# weather-sensor.net
KiCad netlist of a schematic drawn in EAGLE
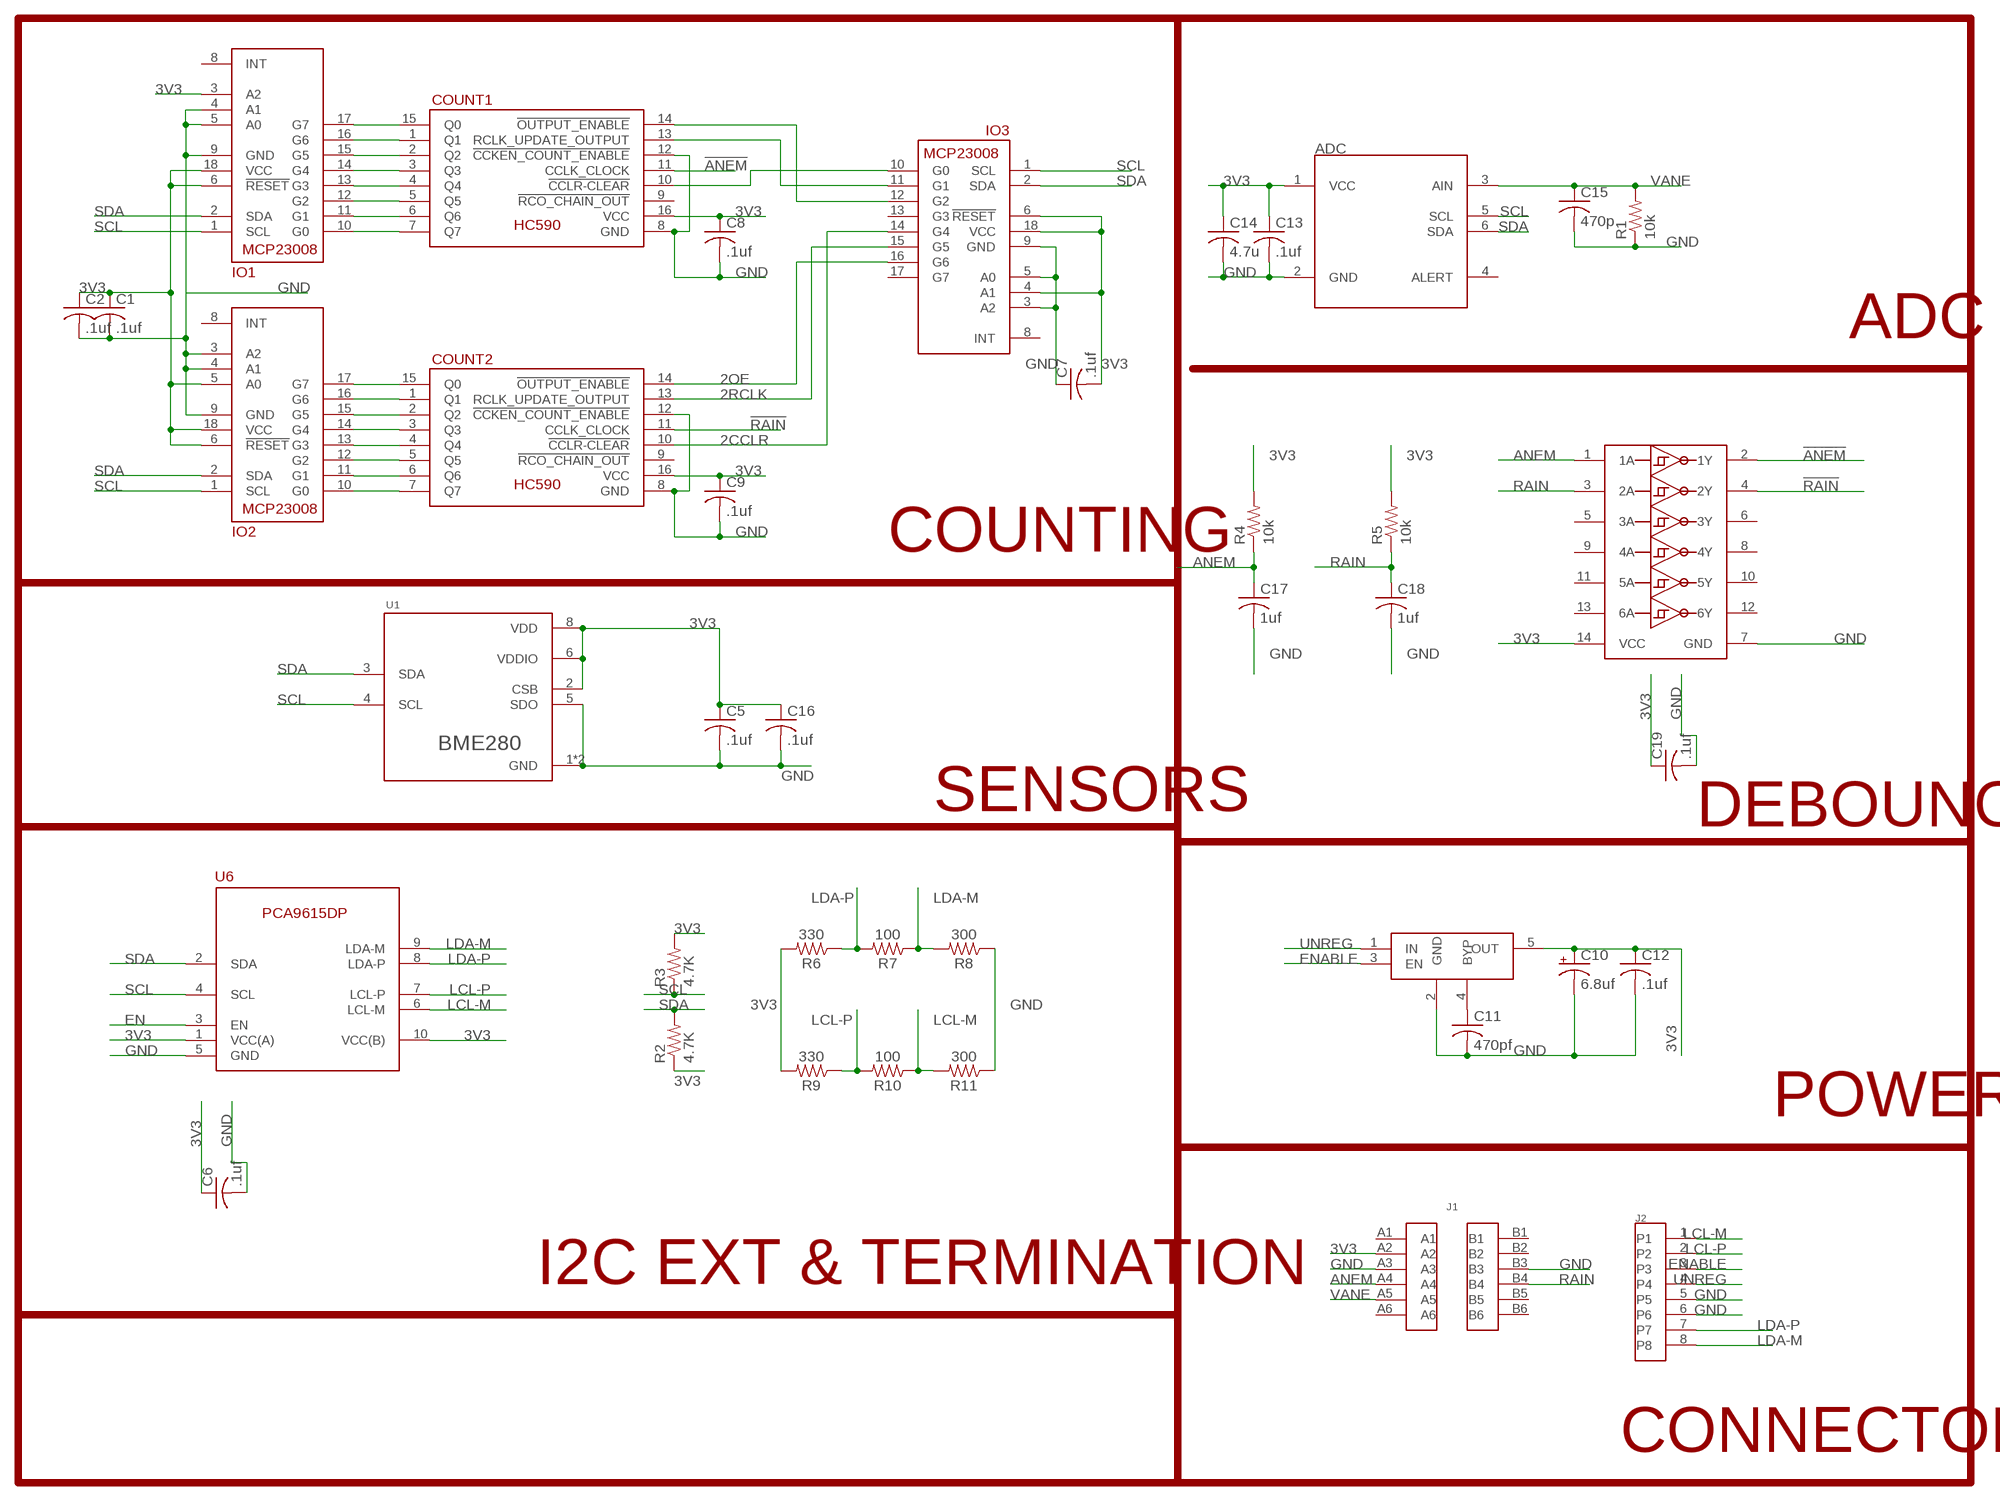
[diagram p0: schematic, sheet 1]

(export (version "E")
  (design (tool "Eeschema 10.0.6"))
  (components
    (comp (ref "ADC")
      (value "ADC081C021SOT-DDC")
      (footprint "eagle-import:SOP95P280X110-6")
      (libsource (lib "eagle-import") (part "ADC081C021SOT-DDC"))
    )
    (comp (ref "C1")
      (value ".1uf")
      (footprint "eagle-import:C0603K")
      (libsource (lib "eagle-import") (part "C-USC0603K"))
    )
    (comp (ref "C2")
      (value ".1uf")
      (footprint "eagle-import:C0603K")
      (libsource (lib "eagle-import") (part "C-USC0603K"))
    )
    (comp (ref "C5")
      (value ".1uf")
      (footprint "eagle-import:C0603K")
      (libsource (lib "eagle-import") (part "C-USC0603K"))
    )
    (comp (ref "C6")
      (value ".1uf")
      (footprint "eagle-import:C0603K")
      (libsource (lib "eagle-import") (part "C-USC0603K"))
    )
    (comp (ref "C7")
      (value ".1uf")
      (footprint "eagle-import:C0603K")
      (libsource (lib "eagle-import") (part "C-USC0603K"))
    )
    (comp (ref "C8")
      (value ".1uf")
      (footprint "eagle-import:C0603K")
      (libsource (lib "eagle-import") (part "C-USC0603K"))
    )
    (comp (ref "C9")
      (value ".1uf")
      (footprint "eagle-import:C0603K")
      (libsource (lib "eagle-import") (part "C-USC0603K"))
    )
    (comp (ref "C10")
      (value "6.8uf")
      (footprint "eagle-import:A_3216-18R")
      (libsource (lib "eagle-import") (part "CPOL-USA/3216-18R"))
    )
    (comp (ref "C11")
      (value "470pf")
      (footprint "eagle-import:C0603K")
      (libsource (lib "eagle-import") (part "C-USC0603K"))
    )
    (comp (ref "C12")
      (value ".1uf")
      (footprint "eagle-import:C0603K")
      (libsource (lib "eagle-import") (part "C-USC0603K"))
    )
    (comp (ref "C13")
      (value ".1uf")
      (footprint "eagle-import:C0603K")
      (libsource (lib "eagle-import") (part "C-USC0603K"))
    )
    (comp (ref "C14")
      (value "4.7u")
      (footprint "eagle-import:C0603K")
      (libsource (lib "eagle-import") (part "C-USC0603K"))
    )
    (comp (ref "C15")
      (value "470p")
      (footprint "eagle-import:C0603K")
      (libsource (lib "eagle-import") (part "C-USC0603K"))
    )
    (comp (ref "C16")
      (value ".1uf")
      (footprint "eagle-import:C0603K")
      (libsource (lib "eagle-import") (part "C-USC0603K"))
    )
    (comp (ref "C17")
      (value "1uf")
      (footprint "eagle-import:C0603K")
      (libsource (lib "eagle-import") (part "C-USC0603K"))
    )
    (comp (ref "C18")
      (value "1uf")
      (footprint "eagle-import:C0603K")
      (libsource (lib "eagle-import") (part "C-USC0603K"))
    )
    (comp (ref "C19")
      (value ".1uf")
      (footprint "eagle-import:C0603K")
      (libsource (lib "eagle-import") (part "C-USC0603K"))
    )
    (comp (ref "COUNT1")
      (value "74HC590")
      (footprint "eagle-import:SOIC127P1050X265-16")
      (libsource (lib "eagle-import") (part "74HC590"))
    )
    (comp (ref "COUNT2")
      (value "74HC590")
      (footprint "eagle-import:SOIC127P1050X265-16")
      (libsource (lib "eagle-import") (part "74HC590"))
    )
    (comp (ref "INVERTER")
      (value "74HC14")
      (footprint "eagle-import:SOIC127P780X200-14")
      (libsource (lib "eagle-import") (part "74HC14"))
    )
    (comp (ref "IO1")
      (value "MCP23008")
      (footprint "eagle-import:SOIC18-W")
      (libsource (lib "eagle-import") (part "MCP23008"))
    )
    (comp (ref "IO2")
      (value "MCP23008")
      (footprint "eagle-import:SOIC18-W")
      (libsource (lib "eagle-import") (part "MCP23008"))
    )
    (comp (ref "IO3")
      (value "MCP23008")
      (footprint "eagle-import:SOIC18-W")
      (libsource (lib "eagle-import") (part "MCP23008"))
    )
    (comp (ref "J1")
      (value "43841-0005")
      (footprint "eagle-import:43841-0005")
      (libsource (lib "eagle-import") (part "43841-0005"))
    )
    (comp (ref "J2")
      (value "95501-6889")
      (footprint "eagle-import:95501-6889")
      (libsource (lib "eagle-import") (part "95501-6889"))
    )
    (comp (ref "R1")
      (value "10k")
      (footprint "eagle-import:R0603")
      (libsource (lib "eagle-import") (part "R-US_R0603"))
    )
    (comp (ref "R2")
      (value "4.7K")
      (footprint "eagle-import:R0603")
      (libsource (lib "eagle-import") (part "R-US_R0603"))
    )
    (comp (ref "R3")
      (value "4.7K")
      (footprint "eagle-import:R0603")
      (libsource (lib "eagle-import") (part "R-US_R0603"))
    )
    (comp (ref "R4")
      (value "10k")
      (footprint "eagle-import:R0603")
      (libsource (lib "eagle-import") (part "R-US_R0603"))
    )
    (comp (ref "R5")
      (value "10k")
      (footprint "eagle-import:R0603")
      (libsource (lib "eagle-import") (part "R-US_R0603"))
    )
    (comp (ref "R6")
      (value "330")
      (footprint "eagle-import:0603")
      (libsource (lib "eagle-import") (part "100KOHM-0603-1/10W-1%"))
    )
    (comp (ref "R7")
      (value "100")
      (footprint "eagle-import:0603")
      (libsource (lib "eagle-import") (part "100KOHM-0603-1/10W-1%"))
    )
    (comp (ref "R8")
      (value "300")
      (footprint "eagle-import:0603")
      (libsource (lib "eagle-import") (part "100KOHM-0603-1/10W-1%"))
    )
    (comp (ref "R9")
      (value "330")
      (footprint "eagle-import:0603")
      (libsource (lib "eagle-import") (part "100KOHM-0603-1/10W-1%"))
    )
    (comp (ref "R10")
      (value "100")
      (footprint "eagle-import:0603")
      (libsource (lib "eagle-import") (part "100KOHM-0603-1/10W-1%"))
    )
    (comp (ref "R11")
      (value "300")
      (footprint "eagle-import:0603")
      (libsource (lib "eagle-import") (part "100KOHM-0603-1/10W-1%"))
    )
    (comp (ref "U1")
      (value "BME280")
      (footprint "eagle-import:BM280")
      (libsource (lib "eagle-import") (part "BME280"))
    )
    (comp (ref "U5")
      (value "MIC5219-3.3YM5-TR")
      (footprint "eagle-import:SOT95P280X145-5")
      (libsource (lib "eagle-import") (part "MIC5219-3.3YM5-TR"))
    )
    (comp (ref "U6")
      (value "PCA9615")
      (footprint "eagle-import:SOP50P490X110-10")
      (libsource (lib "eagle-import") (part "PCA9615"))
    )
  )
  (nets
    (net (code "1") (name "/2CCLR") (class "Default")
      (node (ref "COUNT2") (pin "10") (pinfunction "~{CCLR-CLEAR}_10") (pintype "bidirectional"))
      (node (ref "IO3") (pin "14") (pinfunction "G4_14") (pintype "bidirectional"))
    )
    (net (code "2") (name "/2OE") (class "Default")
      (node (ref "COUNT2") (pin "14") (pinfunction "~{OUTPUT_ENABLE}_14") (pintype "bidirectional"))
      (node (ref "IO3") (pin "16") (pinfunction "G6_16") (pintype "bidirectional"))
    )
    (net (code "3") (name "/2RCLK") (class "Default")
      (node (ref "COUNT2") (pin "13") (pinfunction "RCLK_UPDATE_OUTPUT_13") (pintype "bidirectional"))
      (node (ref "IO3") (pin "15") (pinfunction "G5_15") (pintype "bidirectional"))
    )
    (net (code "4") (name "/3V3") (class "Default")
      (node (ref "ADC") (pin "1") (pinfunction "VCC_1") (pintype "bidirectional"))
      (node (ref "C1") (pin "1") (pinfunction "1_1") (pintype "passive"))
      (node (ref "C10") (pin "+") (pinfunction "+_+") (pintype "passive"))
      (node (ref "C12") (pin "1") (pinfunction "1_1") (pintype "passive"))
      (node (ref "C13") (pin "1") (pinfunction "1_1") (pintype "passive"))
      (node (ref "C14") (pin "1") (pinfunction "1_1") (pintype "passive"))
      (node (ref "C16") (pin "1") (pinfunction "1_1") (pintype "passive"))
      (node (ref "C19") (pin "1") (pinfunction "1_1") (pintype "passive"))
      (node (ref "C2") (pin "1") (pinfunction "1_1") (pintype "passive"))
      (node (ref "C5") (pin "1") (pinfunction "1_1") (pintype "passive"))
      (node (ref "C6") (pin "1") (pinfunction "1_1") (pintype "passive"))
      (node (ref "C7") (pin "2") (pinfunction "2_2") (pintype "passive"))
      (node (ref "C8") (pin "1") (pinfunction "1_1") (pintype "passive"))
      (node (ref "C9") (pin "1") (pinfunction "1_1") (pintype "passive"))
      (node (ref "COUNT1") (pin "16") (pinfunction "VCC_16") (pintype "bidirectional"))
      (node (ref "COUNT2") (pin "16") (pinfunction "VCC_16") (pintype "bidirectional"))
      (node (ref "INVERTER") (pin "14") (pinfunction "VCC_14") (pintype "bidirectional"))
      (node (ref "IO1") (pin "18") (pinfunction "VCC_18") (pintype "bidirectional"))
      (node (ref "IO1") (pin "3") (pinfunction "A2_3") (pintype "bidirectional"))
      (node (ref "IO1") (pin "6") (pinfunction "~{RESET}_6") (pintype "bidirectional"))
      (node (ref "IO2") (pin "18") (pinfunction "VCC_18") (pintype "bidirectional"))
      (node (ref "IO2") (pin "5") (pinfunction "A0_5") (pintype "bidirectional"))
      (node (ref "IO2") (pin "6") (pinfunction "~{RESET}_6") (pintype "bidirectional"))
      (node (ref "IO3") (pin "18") (pinfunction "VCC_18") (pintype "bidirectional"))
      (node (ref "IO3") (pin "4") (pinfunction "A1_4") (pintype "bidirectional"))
      (node (ref "IO3") (pin "6") (pinfunction "~{RESET}_6") (pintype "bidirectional"))
      (node (ref "J1") (pin "A2") (pinfunction "A2_A2") (pintype "bidirectional"))
      (node (ref "R2") (pin "1") (pinfunction "1_1") (pintype "passive"))
      (node (ref "R3") (pin "2") (pinfunction "2_2") (pintype "passive"))
      (node (ref "R4") (pin "2") (pinfunction "2_2") (pintype "passive"))
      (node (ref "R5") (pin "2") (pinfunction "2_2") (pintype "passive"))
      (node (ref "R6") (pin "2") (pinfunction "2_2") (pintype "passive"))
      (node (ref "R9") (pin "2") (pinfunction "2_2") (pintype "passive"))
      (node (ref "U1") (pin "2") (pinfunction "CSB_2") (pintype "bidirectional"))
      (node (ref "U1") (pin "6") (pinfunction "VDDIO_6") (pintype "bidirectional"))
      (node (ref "U1") (pin "8") (pinfunction "VDD_8") (pintype "bidirectional"))
      (node (ref "U5") (pin "5") (pinfunction "OUT_5") (pintype "bidirectional"))
      (node (ref "U6") (pin "1") (pinfunction "VCC(A)_1") (pintype "bidirectional"))
      (node (ref "U6") (pin "10") (pinfunction "VCC(B)_10") (pintype "bidirectional"))
    )
    (net (code "5") (name "/ANEM") (class "Default")
      (node (ref "C17") (pin "1") (pinfunction "1_1") (pintype "passive"))
      (node (ref "INVERTER") (pin "1") (pinfunction "1A_1") (pintype "bidirectional"))
      (node (ref "J1") (pin "A4") (pinfunction "A4_A4") (pintype "bidirectional"))
      (node (ref "R4") (pin "1") (pinfunction "1_1") (pintype "passive"))
    )
    (net (code "6") (name "/EN") (class "Default")
      (node (ref "U6") (pin "3") (pinfunction "EN_3") (pintype "bidirectional"))
    )
    (net (code "7") (name "/ENABLE") (class "Default")
      (node (ref "J2") (pin "3") (pinfunction "P3_3") (pintype "bidirectional"))
      (node (ref "U5") (pin "3") (pinfunction "EN_3") (pintype "bidirectional"))
    )
    (net (code "8") (name "/GND") (class "Default")
      (node (ref "ADC") (pin "2") (pinfunction "GND_2") (pintype "bidirectional"))
      (node (ref "C1") (pin "2") (pinfunction "2_2") (pintype "passive"))
      (node (ref "C10") (pin "-") (pinfunction "-_-") (pintype "passive"))
      (node (ref "C11") (pin "2") (pinfunction "2_2") (pintype "passive"))
      (node (ref "C12") (pin "2") (pinfunction "2_2") (pintype "passive"))
      (node (ref "C13") (pin "2") (pinfunction "2_2") (pintype "passive"))
      (node (ref "C14") (pin "2") (pinfunction "2_2") (pintype "passive"))
      (node (ref "C15") (pin "2") (pinfunction "2_2") (pintype "passive"))
      (node (ref "C16") (pin "2") (pinfunction "2_2") (pintype "passive"))
      (node (ref "C17") (pin "2") (pinfunction "2_2") (pintype "passive"))
      (node (ref "C18") (pin "2") (pinfunction "2_2") (pintype "passive"))
      (node (ref "C19") (pin "2") (pinfunction "2_2") (pintype "passive"))
      (node (ref "C2") (pin "2") (pinfunction "2_2") (pintype "passive"))
      (node (ref "C5") (pin "2") (pinfunction "2_2") (pintype "passive"))
      (node (ref "C6") (pin "2") (pinfunction "2_2") (pintype "passive"))
      (node (ref "C7") (pin "1") (pinfunction "1_1") (pintype "passive"))
      (node (ref "C8") (pin "2") (pinfunction "2_2") (pintype "passive"))
      (node (ref "C9") (pin "2") (pinfunction "2_2") (pintype "passive"))
      (node (ref "COUNT1") (pin "12") (pinfunction "~{CCKEN_COUNT_ENABLE}_12") (pintype "bidirectional"))
      (node (ref "COUNT1") (pin "8") (pinfunction "GND_8") (pintype "bidirectional"))
      (node (ref "COUNT2") (pin "12") (pinfunction "~{CCKEN_COUNT_ENABLE}_12") (pintype "bidirectional"))
      (node (ref "COUNT2") (pin "8") (pinfunction "GND_8") (pintype "bidirectional"))
      (node (ref "INVERTER") (pin "7") (pinfunction "GND_7") (pintype "bidirectional"))
      (node (ref "IO1") (pin "4") (pinfunction "A1_4") (pintype "bidirectional"))
      (node (ref "IO1") (pin "5") (pinfunction "A0_5") (pintype "bidirectional"))
      (node (ref "IO1") (pin "9") (pinfunction "GND_9") (pintype "bidirectional"))
      (node (ref "IO2") (pin "3") (pinfunction "A2_3") (pintype "bidirectional"))
      (node (ref "IO2") (pin "4") (pinfunction "A1_4") (pintype "bidirectional"))
      (node (ref "IO2") (pin "9") (pinfunction "GND_9") (pintype "bidirectional"))
      (node (ref "IO3") (pin "3") (pinfunction "A2_3") (pintype "bidirectional"))
      (node (ref "IO3") (pin "5") (pinfunction "A0_5") (pintype "bidirectional"))
      (node (ref "IO3") (pin "9") (pinfunction "GND_9") (pintype "bidirectional"))
      (node (ref "J1") (pin "A3") (pinfunction "A3_A3") (pintype "bidirectional"))
      (node (ref "J1") (pin "B3") (pinfunction "B3_B3") (pintype "bidirectional"))
      (node (ref "J2") (pin "5") (pinfunction "P5_5") (pintype "bidirectional"))
      (node (ref "J2") (pin "6") (pinfunction "P6_6") (pintype "bidirectional"))
      (node (ref "R1") (pin "1") (pinfunction "1_1") (pintype "passive"))
      (node (ref "R11") (pin "1") (pinfunction "1_1") (pintype "passive"))
      (node (ref "R8") (pin "1") (pinfunction "1_1") (pintype "passive"))
      (node (ref "U1") (pin "1") (pinfunction "GND_1") (pintype "bidirectional"))
      (node (ref "U1") (pin "5") (pinfunction "SDO_5") (pintype "bidirectional"))
      (node (ref "U1") (pin "7") (pinfunction "GND_7") (pintype "bidirectional"))
      (node (ref "U5") (pin "2") (pinfunction "GND_2") (pintype "bidirectional"))
      (node (ref "U6") (pin "5") (pinfunction "GND_5") (pintype "bidirectional"))
    )
    (net (code "9") (name "/LCL-M") (class "Default")
      (node (ref "J2") (pin "1") (pinfunction "P1_1") (pintype "bidirectional"))
      (node (ref "R10") (pin "1") (pinfunction "1_1") (pintype "passive"))
      (node (ref "R11") (pin "2") (pinfunction "2_2") (pintype "passive"))
      (node (ref "U6") (pin "6") (pinfunction "LCL-M_6") (pintype "bidirectional"))
    )
    (net (code "10") (name "/LCL-P") (class "Default")
      (node (ref "J2") (pin "2") (pinfunction "P2_2") (pintype "bidirectional"))
      (node (ref "R10") (pin "2") (pinfunction "2_2") (pintype "passive"))
      (node (ref "R9") (pin "1") (pinfunction "1_1") (pintype "passive"))
      (node (ref "U6") (pin "7") (pinfunction "LCL-P_7") (pintype "bidirectional"))
    )
    (net (code "11") (name "/LDA-M") (class "Default")
      (node (ref "J2") (pin "8") (pinfunction "P8_8") (pintype "bidirectional"))
      (node (ref "R7") (pin "1") (pinfunction "1_1") (pintype "passive"))
      (node (ref "R8") (pin "2") (pinfunction "2_2") (pintype "passive"))
      (node (ref "U6") (pin "9") (pinfunction "LDA-M_9") (pintype "bidirectional"))
    )
    (net (code "12") (name "/LDA-P") (class "Default")
      (node (ref "J2") (pin "7") (pinfunction "P7_7") (pintype "bidirectional"))
      (node (ref "R6") (pin "1") (pinfunction "1_1") (pintype "passive"))
      (node (ref "R7") (pin "2") (pinfunction "2_2") (pintype "passive"))
      (node (ref "U6") (pin "8") (pinfunction "LDA-P_8") (pintype "bidirectional"))
    )
    (net (code "13") (name "/RAIN") (class "Default")
      (node (ref "C18") (pin "1") (pinfunction "1_1") (pintype "passive"))
      (node (ref "INVERTER") (pin "3") (pinfunction "2A_3") (pintype "bidirectional"))
      (node (ref "J1") (pin "B4") (pinfunction "B4_B4") (pintype "bidirectional"))
      (node (ref "R5") (pin "1") (pinfunction "1_1") (pintype "passive"))
    )
    (net (code "14") (name "/SCL") (class "Default")
      (node (ref "ADC") (pin "5") (pinfunction "SCL_5") (pintype "bidirectional"))
      (node (ref "IO1") (pin "1") (pinfunction "SCL_1") (pintype "bidirectional"))
      (node (ref "IO2") (pin "1") (pinfunction "SCL_1") (pintype "bidirectional"))
      (node (ref "IO3") (pin "1") (pinfunction "SCL_1") (pintype "bidirectional"))
      (node (ref "R3") (pin "1") (pinfunction "1_1") (pintype "passive"))
      (node (ref "U1") (pin "4") (pinfunction "SCL_4") (pintype "bidirectional"))
      (node (ref "U6") (pin "4") (pinfunction "SCL_4") (pintype "bidirectional"))
    )
    (net (code "15") (name "/SDA") (class "Default")
      (node (ref "ADC") (pin "6") (pinfunction "SDA_6") (pintype "bidirectional"))
      (node (ref "IO1") (pin "2") (pinfunction "SDA_2") (pintype "bidirectional"))
      (node (ref "IO2") (pin "2") (pinfunction "SDA_2") (pintype "bidirectional"))
      (node (ref "IO3") (pin "2") (pinfunction "SDA_2") (pintype "bidirectional"))
      (node (ref "R2") (pin "2") (pinfunction "2_2") (pintype "passive"))
      (node (ref "U1") (pin "3") (pinfunction "SDA_3") (pintype "bidirectional"))
      (node (ref "U6") (pin "2") (pinfunction "SDA_2") (pintype "bidirectional"))
    )
    (net (code "16") (name "/UNREG") (class "Default")
      (node (ref "J2") (pin "4") (pinfunction "P4_4") (pintype "bidirectional"))
      (node (ref "U5") (pin "1") (pinfunction "IN_1") (pintype "bidirectional"))
    )
    (net (code "17") (name "/VANE") (class "Default")
      (node (ref "ADC") (pin "3") (pinfunction "AIN_3") (pintype "bidirectional"))
      (node (ref "C15") (pin "1") (pinfunction "1_1") (pintype "passive"))
      (node (ref "J1") (pin "A5") (pinfunction "A5_A5") (pintype "bidirectional"))
      (node (ref "R1") (pin "2") (pinfunction "2_2") (pintype "passive"))
    )
    (net (code "18") (name "/~{ANEM}") (class "Default")
      (node (ref "COUNT1") (pin "11") (pinfunction "CCLK_CLOCK_11") (pintype "bidirectional"))
      (node (ref "INVERTER") (pin "2") (pinfunction "1Y_2") (pintype "bidirectional"))
    )
    (net (code "19") (name "/~{RAIN}") (class "Default")
      (node (ref "COUNT2") (pin "11") (pinfunction "CCLK_CLOCK_11") (pintype "bidirectional"))
      (node (ref "INVERTER") (pin "4") (pinfunction "2Y_4") (pintype "bidirectional"))
    )
    (net (code "20") (name "Net-(COUNT1-Q0)") (class "Default")
      (node (ref "COUNT1") (pin "15") (pinfunction "Q0_15") (pintype "bidirectional"))
      (node (ref "IO1") (pin "17") (pinfunction "G7_17") (pintype "bidirectional"))
    )
    (net (code "21") (name "Net-(COUNT1-Q1)") (class "Default")
      (node (ref "COUNT1") (pin "1") (pinfunction "Q1_1") (pintype "bidirectional"))
      (node (ref "IO1") (pin "16") (pinfunction "G6_16") (pintype "bidirectional"))
    )
    (net (code "22") (name "Net-(COUNT1-Q2)") (class "Default")
      (node (ref "COUNT1") (pin "2") (pinfunction "Q2_2") (pintype "bidirectional"))
      (node (ref "IO1") (pin "15") (pinfunction "G5_15") (pintype "bidirectional"))
    )
    (net (code "23") (name "Net-(COUNT1-Q3)") (class "Default")
      (node (ref "COUNT1") (pin "3") (pinfunction "Q3_3") (pintype "bidirectional"))
      (node (ref "IO1") (pin "14") (pinfunction "G4_14") (pintype "bidirectional"))
    )
    (net (code "24") (name "Net-(COUNT1-Q4)") (class "Default")
      (node (ref "COUNT1") (pin "4") (pinfunction "Q4_4") (pintype "bidirectional"))
      (node (ref "IO1") (pin "13") (pinfunction "G3_13") (pintype "bidirectional"))
    )
    (net (code "25") (name "Net-(COUNT1-Q5)") (class "Default")
      (node (ref "COUNT1") (pin "5") (pinfunction "Q5_5") (pintype "bidirectional"))
      (node (ref "IO1") (pin "12") (pinfunction "G2_12") (pintype "bidirectional"))
    )
    (net (code "26") (name "Net-(COUNT1-Q6)") (class "Default")
      (node (ref "COUNT1") (pin "6") (pinfunction "Q6_6") (pintype "bidirectional"))
      (node (ref "IO1") (pin "11") (pinfunction "G1_11") (pintype "bidirectional"))
    )
    (net (code "27") (name "Net-(COUNT1-Q7)") (class "Default")
      (node (ref "COUNT1") (pin "7") (pinfunction "Q7_7") (pintype "bidirectional"))
      (node (ref "IO1") (pin "10") (pinfunction "G0_10") (pintype "bidirectional"))
    )
    (net (code "28") (name "Net-(COUNT1-RCLK_UPDATE_OUTPUT)") (class "Default")
      (node (ref "COUNT1") (pin "13") (pinfunction "RCLK_UPDATE_OUTPUT_13") (pintype "bidirectional"))
      (node (ref "IO3") (pin "11") (pinfunction "G1_11") (pintype "bidirectional"))
    )
    (net (code "29") (name "Net-(COUNT1-~{CCLR-CLEAR})") (class "Default")
      (node (ref "COUNT1") (pin "10") (pinfunction "~{CCLR-CLEAR}_10") (pintype "bidirectional"))
      (node (ref "IO3") (pin "10") (pinfunction "G0_10") (pintype "bidirectional"))
    )
    (net (code "30") (name "Net-(COUNT1-~{OUTPUT_ENABLE})") (class "Default")
      (node (ref "COUNT1") (pin "14") (pinfunction "~{OUTPUT_ENABLE}_14") (pintype "bidirectional"))
      (node (ref "IO3") (pin "12") (pinfunction "G2_12") (pintype "bidirectional"))
    )
    (net (code "31") (name "Net-(COUNT2-Q0)") (class "Default")
      (node (ref "COUNT2") (pin "15") (pinfunction "Q0_15") (pintype "bidirectional"))
      (node (ref "IO2") (pin "17") (pinfunction "G7_17") (pintype "bidirectional"))
    )
    (net (code "32") (name "Net-(COUNT2-Q1)") (class "Default")
      (node (ref "COUNT2") (pin "1") (pinfunction "Q1_1") (pintype "bidirectional"))
      (node (ref "IO2") (pin "16") (pinfunction "G6_16") (pintype "bidirectional"))
    )
    (net (code "33") (name "Net-(COUNT2-Q2)") (class "Default")
      (node (ref "COUNT2") (pin "2") (pinfunction "Q2_2") (pintype "bidirectional"))
      (node (ref "IO2") (pin "15") (pinfunction "G5_15") (pintype "bidirectional"))
    )
    (net (code "34") (name "Net-(COUNT2-Q3)") (class "Default")
      (node (ref "COUNT2") (pin "3") (pinfunction "Q3_3") (pintype "bidirectional"))
      (node (ref "IO2") (pin "14") (pinfunction "G4_14") (pintype "bidirectional"))
    )
    (net (code "35") (name "Net-(COUNT2-Q4)") (class "Default")
      (node (ref "COUNT2") (pin "4") (pinfunction "Q4_4") (pintype "bidirectional"))
      (node (ref "IO2") (pin "13") (pinfunction "G3_13") (pintype "bidirectional"))
    )
    (net (code "36") (name "Net-(COUNT2-Q5)") (class "Default")
      (node (ref "COUNT2") (pin "5") (pinfunction "Q5_5") (pintype "bidirectional"))
      (node (ref "IO2") (pin "12") (pinfunction "G2_12") (pintype "bidirectional"))
    )
    (net (code "37") (name "Net-(COUNT2-Q6)") (class "Default")
      (node (ref "COUNT2") (pin "6") (pinfunction "Q6_6") (pintype "bidirectional"))
      (node (ref "IO2") (pin "11") (pinfunction "G1_11") (pintype "bidirectional"))
    )
    (net (code "38") (name "Net-(COUNT2-Q7)") (class "Default")
      (node (ref "COUNT2") (pin "7") (pinfunction "Q7_7") (pintype "bidirectional"))
      (node (ref "IO2") (pin "10") (pinfunction "G0_10") (pintype "bidirectional"))
    )
    (net (code "39") (name "Net-(U5-BYP)") (class "Default")
      (node (ref "C11") (pin "1") (pinfunction "1_1") (pintype "passive"))
      (node (ref "U5") (pin "4") (pinfunction "BYP_4") (pintype "bidirectional"))
    )
    (net (code "40") (name "unconnected-(ADC-ALERT-Pad4)") (class "Default")
      (node (ref "ADC") (pin "4") (pinfunction "ALERT_4") (pintype "bidirectional"))
    )
    (net (code "41") (name "unconnected-(COUNT1-~{RCO_CHAIN_OUT}-Pad9)") (class "Default")
      (node (ref "COUNT1") (pin "9") (pinfunction "~{RCO_CHAIN_OUT}_9") (pintype "bidirectional"))
    )
    (net (code "42") (name "unconnected-(COUNT2-~{RCO_CHAIN_OUT}-Pad9)") (class "Default")
      (node (ref "COUNT2") (pin "9") (pinfunction "~{RCO_CHAIN_OUT}_9") (pintype "bidirectional"))
    )
    (net (code "43") (name "unconnected-(INVERTER-3A-Pad5)") (class "Default")
      (node (ref "INVERTER") (pin "5") (pinfunction "3A_5") (pintype "bidirectional"))
    )
    (net (code "44") (name "unconnected-(INVERTER-3Y-Pad6)") (class "Default")
      (node (ref "INVERTER") (pin "6") (pinfunction "3Y_6") (pintype "bidirectional"))
    )
    (net (code "45") (name "unconnected-(INVERTER-4A-Pad9)") (class "Default")
      (node (ref "INVERTER") (pin "9") (pinfunction "4A_9") (pintype "bidirectional"))
    )
    (net (code "46") (name "unconnected-(INVERTER-4Y-Pad8)") (class "Default")
      (node (ref "INVERTER") (pin "8") (pinfunction "4Y_8") (pintype "bidirectional"))
    )
    (net (code "47") (name "unconnected-(INVERTER-5A-Pad11)") (class "Default")
      (node (ref "INVERTER") (pin "11") (pinfunction "5A_11") (pintype "bidirectional"))
    )
    (net (code "48") (name "unconnected-(INVERTER-5Y-Pad10)") (class "Default")
      (node (ref "INVERTER") (pin "10") (pinfunction "5Y_10") (pintype "bidirectional"))
    )
    (net (code "49") (name "unconnected-(INVERTER-6A-Pad13)") (class "Default")
      (node (ref "INVERTER") (pin "13") (pinfunction "6A_13") (pintype "bidirectional"))
    )
    (net (code "50") (name "unconnected-(INVERTER-6Y-Pad12)") (class "Default")
      (node (ref "INVERTER") (pin "12") (pinfunction "6Y_12") (pintype "bidirectional"))
    )
    (net (code "51") (name "unconnected-(IO1-INT-Pad8)") (class "Default")
      (node (ref "IO1") (pin "8") (pinfunction "INT_8") (pintype "bidirectional"))
    )
    (net (code "52") (name "unconnected-(IO2-INT-Pad8)") (class "Default")
      (node (ref "IO2") (pin "8") (pinfunction "INT_8") (pintype "bidirectional"))
    )
    (net (code "53") (name "unconnected-(IO3-G3-Pad13)") (class "Default")
      (node (ref "IO3") (pin "13") (pinfunction "G3_13") (pintype "bidirectional"))
    )
    (net (code "54") (name "unconnected-(IO3-G7-Pad17)") (class "Default")
      (node (ref "IO3") (pin "17") (pinfunction "G7_17") (pintype "bidirectional"))
    )
    (net (code "55") (name "unconnected-(IO3-INT-Pad8)") (class "Default")
      (node (ref "IO3") (pin "8") (pinfunction "INT_8") (pintype "bidirectional"))
    )
    (net (code "56") (name "unconnected-(J1-PadA1)") (class "Default")
      (node (ref "J1") (pin "A1") (pinfunction "A1_A1") (pintype "bidirectional"))
    )
    (net (code "57") (name "unconnected-(J1-PadA6)") (class "Default")
      (node (ref "J1") (pin "A6") (pinfunction "A6_A6") (pintype "bidirectional"))
    )
    (net (code "58") (name "unconnected-(J1-PadB1)") (class "Default")
      (node (ref "J1") (pin "B1") (pinfunction "B1_B1") (pintype "bidirectional"))
    )
    (net (code "59") (name "unconnected-(J1-PadB2)") (class "Default")
      (node (ref "J1") (pin "B2") (pinfunction "B2_B2") (pintype "bidirectional"))
    )
    (net (code "60") (name "unconnected-(J1-PadB5)") (class "Default")
      (node (ref "J1") (pin "B5") (pinfunction "B5_B5") (pintype "bidirectional"))
    )
    (net (code "61") (name "unconnected-(J1-PadB6)") (class "Default")
      (node (ref "J1") (pin "B6") (pinfunction "B6_B6") (pintype "bidirectional"))
    )
  )
)
